# old_motor_line.net
KiCad netlist of a schematic drawn in EAGLE
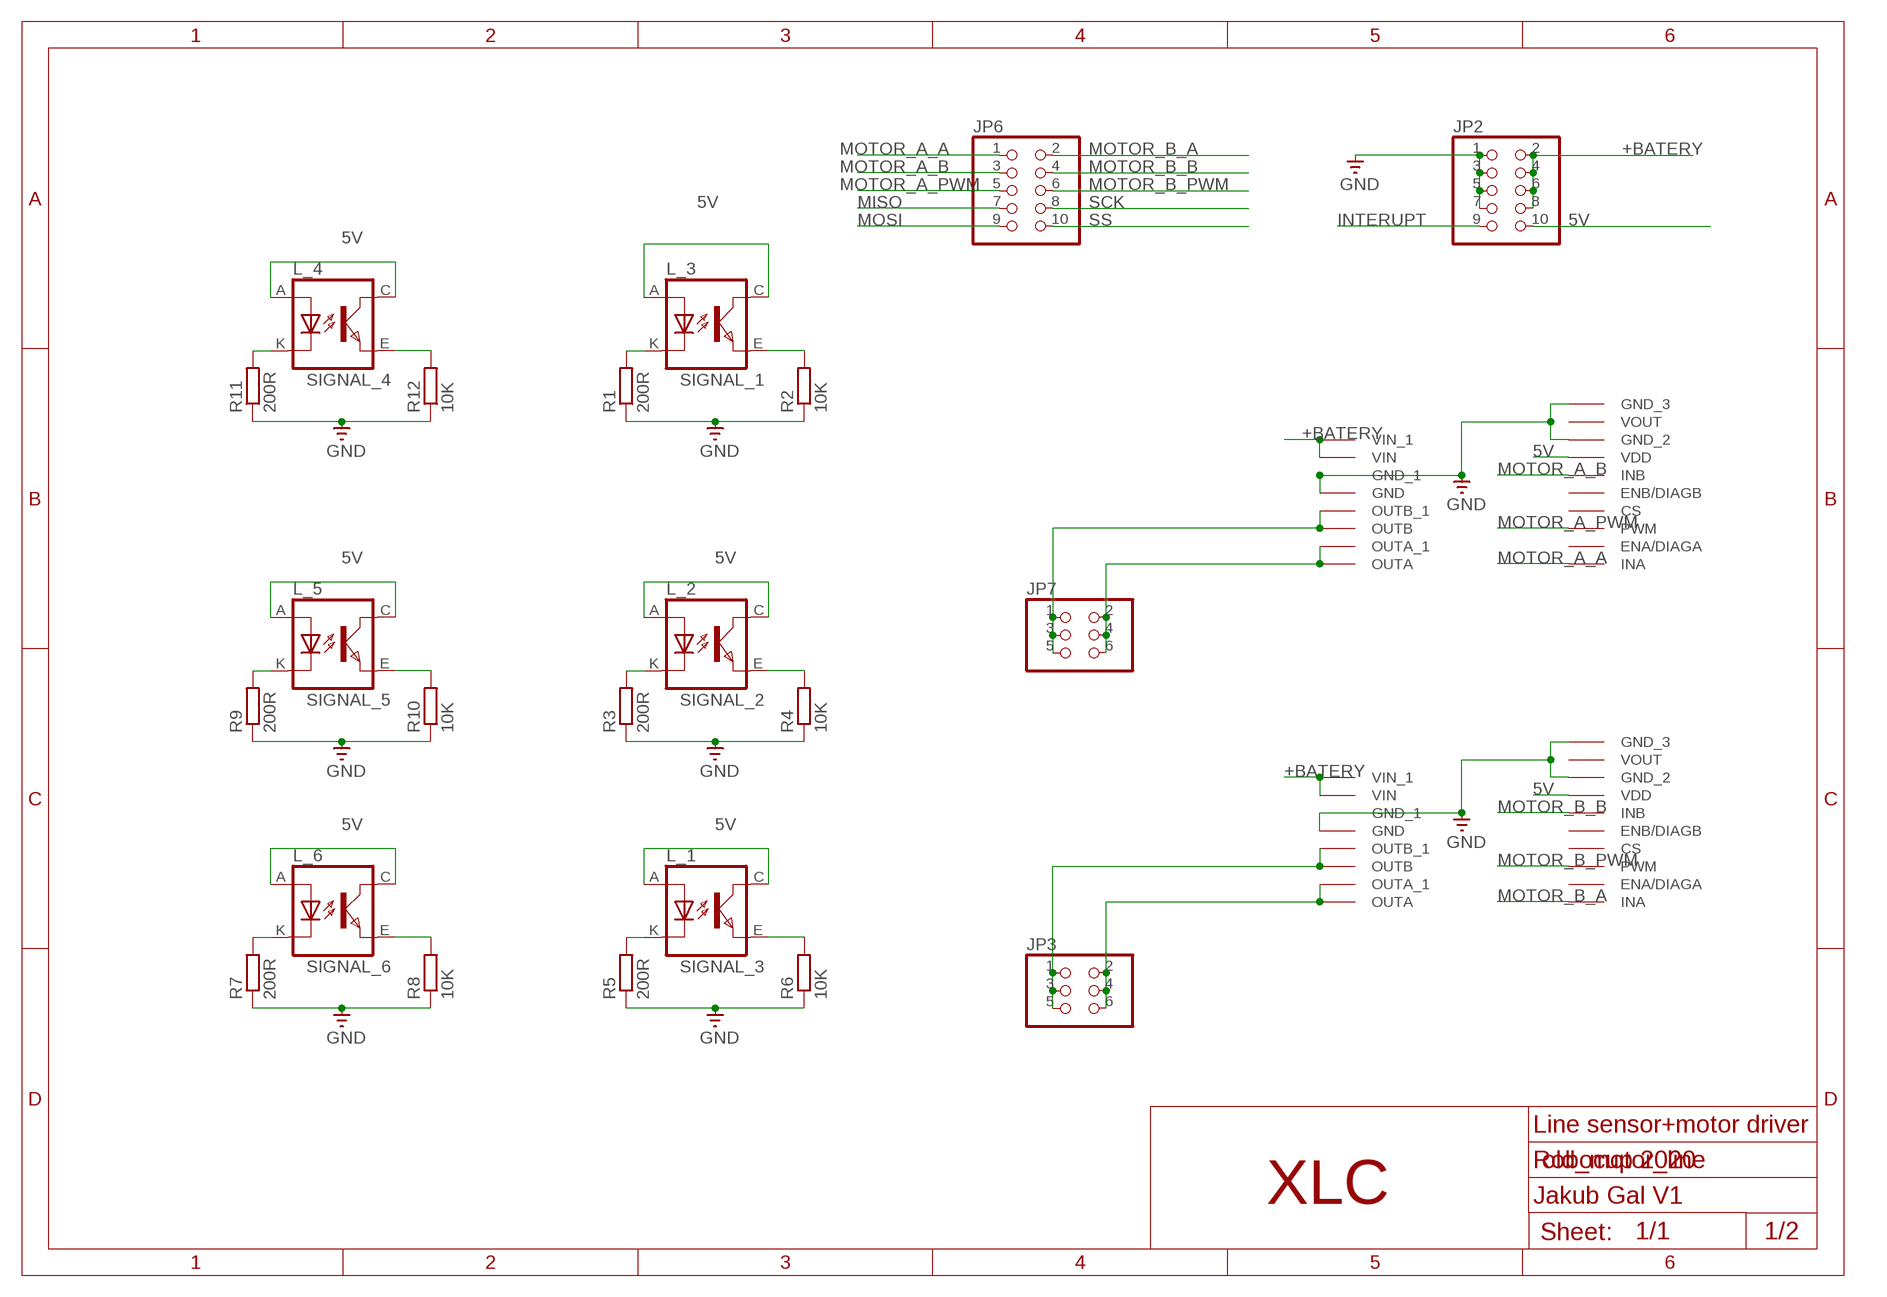
[diagram p0: schematic, sheet 1, part 1 of 2]
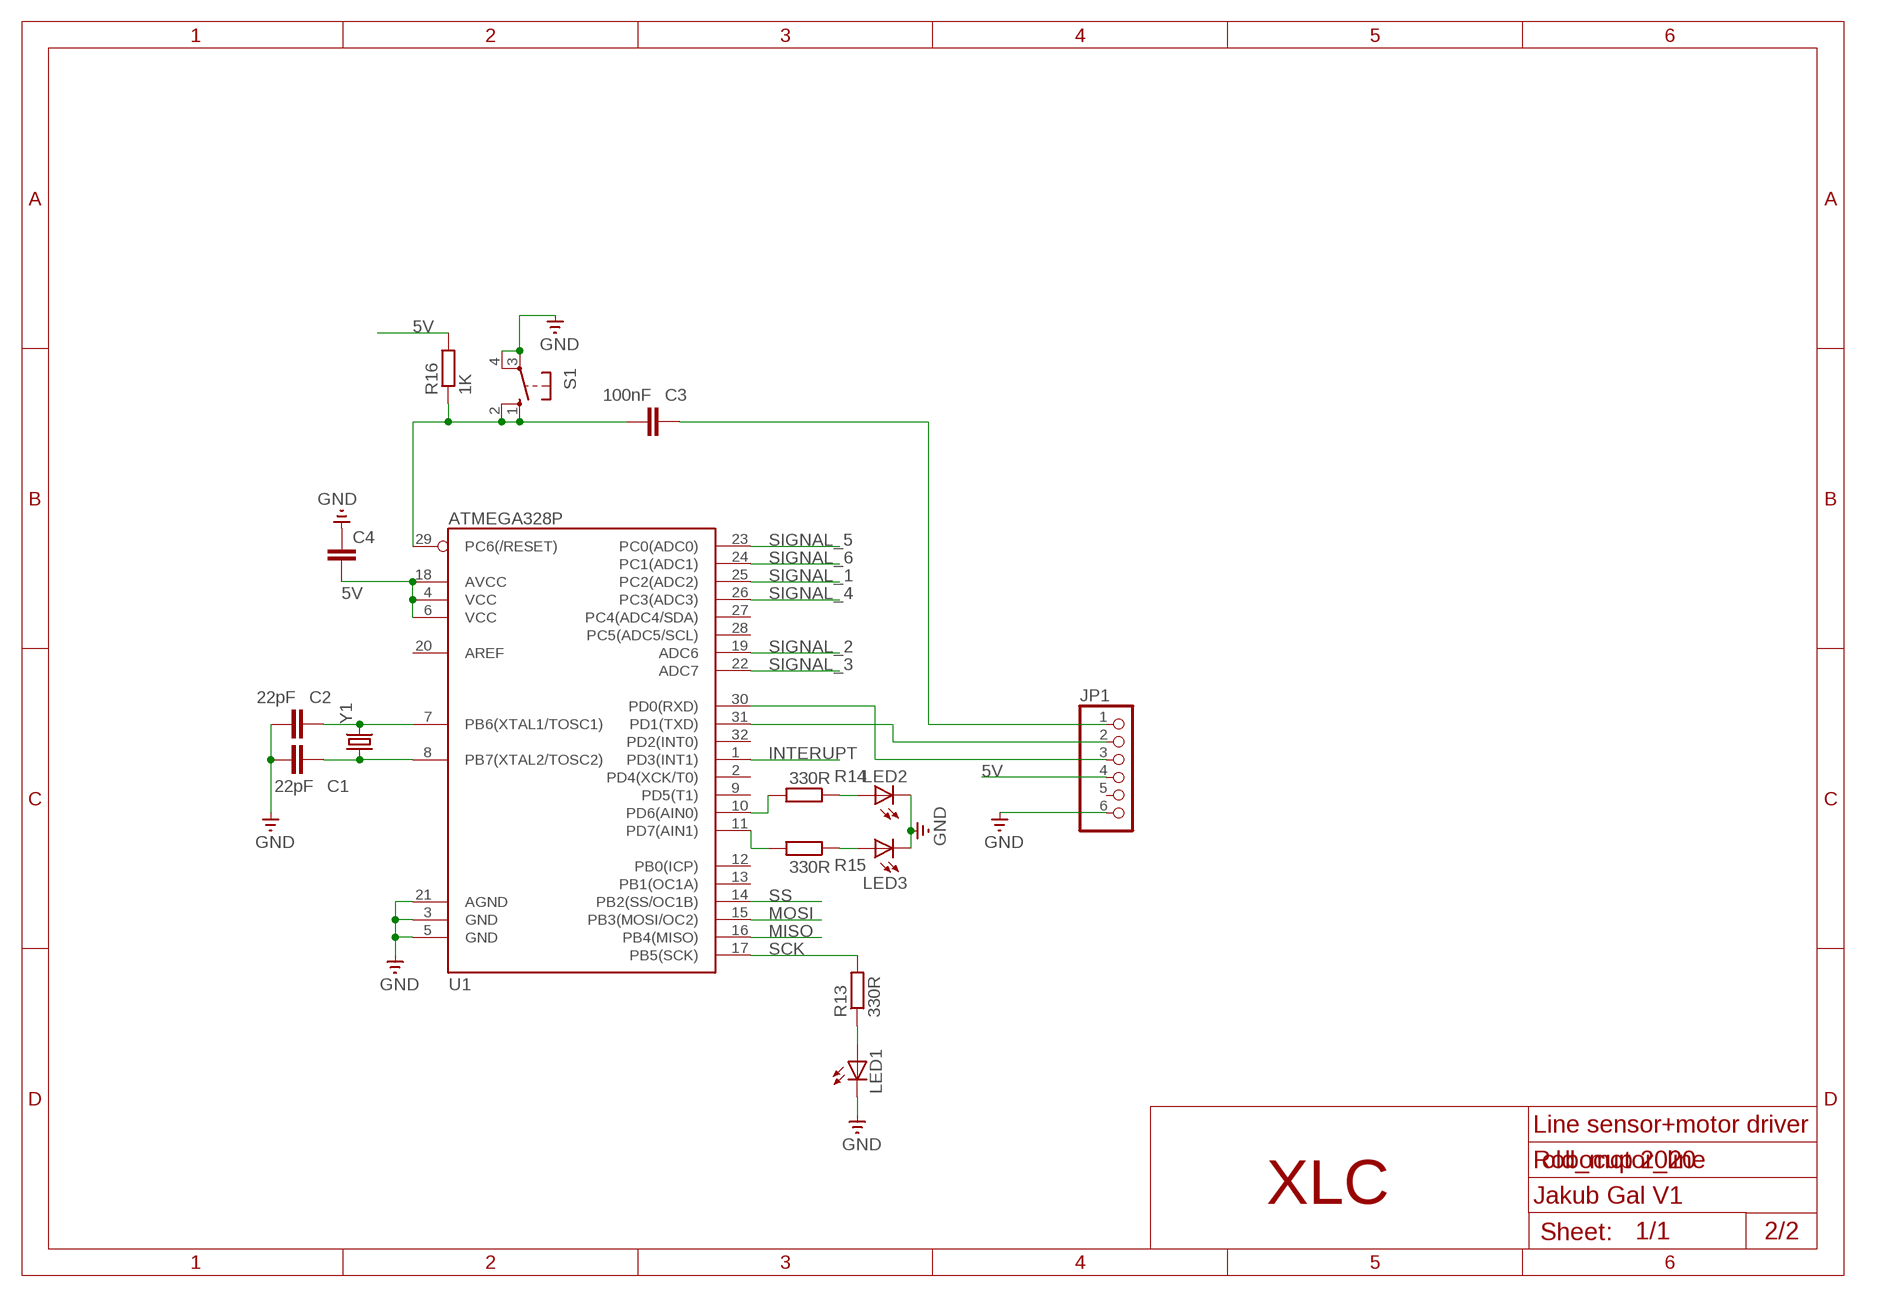
[diagram p1: schematic, sheet 1, part 2 of 2]

(export (version "E")
  (design (tool "Eeschema 10.0.6"))
  (components
    (comp (ref "C1")
      (value "22pF")
      (footprint "eagle-import:C0603")
      (libsource (lib "eagle-import") (part "rcl@1_C-EUC0603"))
    )
    (comp (ref "C2")
      (value "22pF")
      (footprint "eagle-import:C0603")
      (libsource (lib "eagle-import") (part "rcl@1_C-EUC0603"))
    )
    (comp (ref "C3")
      (value "100nF")
      (footprint "eagle-import:C0603")
      (libsource (lib "eagle-import") (part "rcl@1_C-EUC0603"))
    )
    (comp (ref "C4")
      (value "C-EUC0603")
      (footprint "eagle-import:C0603")
      (libsource (lib "eagle-import") (part "C-EUC0603"))
    )
    (comp (ref "JP1")
      (value "PINHD-1X6/90")
      (footprint "eagle-import:1X06_90")
      (libsource (lib "eagle-import") (part "PINHD-1X6/90"))
    )
    (comp (ref "JP2")
      (value "PINHD-2X5IDC")
      (footprint "eagle-import:2X05_IDC")
      (libsource (lib "eagle-import") (part "PINHD-2X5IDC"))
    )
    (comp (ref "JP3")
      (value "PINHD-2X3IDC")
      (footprint "eagle-import:2X03_IDC")
      (libsource (lib "eagle-import") (part "PINHD-2X3IDC"))
    )
    (comp (ref "JP6")
      (value "PINHD-2X5IDC")
      (footprint "eagle-import:2X05_IDC")
      (libsource (lib "eagle-import") (part "PINHD-2X5IDC"))
    )
    (comp (ref "JP7")
      (value "PINHD-2X3IDC")
      (footprint "eagle-import:2X03_IDC")
      (libsource (lib "eagle-import") (part "PINHD-2X3IDC"))
    )
    (comp (ref "LED1")
      (value "LEDCHIPLED_0603")
      (footprint "eagle-import:CHIPLED_0603")
      (libsource (lib "eagle-import") (part "LEDCHIPLED_0603"))
    )
    (comp (ref "LED2")
      (value "LEDCHIPLED_0603")
      (footprint "eagle-import:CHIPLED_0603")
      (libsource (lib "eagle-import") (part "LEDCHIPLED_0603"))
    )
    (comp (ref "LED3")
      (value "LEDCHIPLED_0603")
      (footprint "eagle-import:CHIPLED_0603")
      (libsource (lib "eagle-import") (part "LEDCHIPLED_0603"))
    )
    (comp (ref "L_1")
      (value "TCRT5000")
      (footprint "eagle-import:TCRT5000")
      (libsource (lib "eagle-import") (part "TCRT5000"))
    )
    (comp (ref "L_2")
      (value "TCRT5000")
      (footprint "eagle-import:TCRT5000")
      (libsource (lib "eagle-import") (part "TCRT5000"))
    )
    (comp (ref "L_3")
      (value "TCRT5000")
      (footprint "eagle-import:TCRT5000")
      (libsource (lib "eagle-import") (part "TCRT5000"))
    )
    (comp (ref "L_4")
      (value "TCRT5000")
      (footprint "eagle-import:TCRT5000")
      (fields (field (name "SPICEPREFIX") "O"))
      (libsource (lib "eagle-import") (part "TCRT5000"))
    )
    (comp (ref "L_5")
      (value "TCRT5000")
      (footprint "eagle-import:TCRT5000")
      (libsource (lib "eagle-import") (part "TCRT5000"))
    )
    (comp (ref "L_6")
      (value "TCRT5000")
      (footprint "eagle-import:TCRT5000")
      (fields (field (name "SPICEPREFIX") "O"))
      (libsource (lib "eagle-import") (part "TCRT5000"))
    )
    (comp (ref "R1")
      (value "200R")
      (footprint "eagle-import:R0603")
      (libsource (lib "eagle-import") (part "R-EU_R0603"))
    )
    (comp (ref "R2")
      (value "10K")
      (footprint "eagle-import:R0603")
      (libsource (lib "eagle-import") (part "R-EU_R0603"))
    )
    (comp (ref "R3")
      (value "200R")
      (footprint "eagle-import:R0603")
      (libsource (lib "eagle-import") (part "R-EU_R0603"))
    )
    (comp (ref "R4")
      (value "10K")
      (footprint "eagle-import:R0603")
      (libsource (lib "eagle-import") (part "R-EU_R0603"))
    )
    (comp (ref "R5")
      (value "200R")
      (footprint "eagle-import:R0603")
      (libsource (lib "eagle-import") (part "R-EU_R0603"))
    )
    (comp (ref "R6")
      (value "10K")
      (footprint "eagle-import:R0603")
      (libsource (lib "eagle-import") (part "R-EU_R0603"))
    )
    (comp (ref "R7")
      (value "200R")
      (footprint "eagle-import:R0603")
      (libsource (lib "eagle-import") (part "R-EU_R0603"))
    )
    (comp (ref "R8")
      (value "10K")
      (footprint "eagle-import:R0603")
      (libsource (lib "eagle-import") (part "R-EU_R0603"))
    )
    (comp (ref "R9")
      (value "200R")
      (footprint "eagle-import:R0603")
      (libsource (lib "eagle-import") (part "R-EU_R0603"))
    )
    (comp (ref "R10")
      (value "10K")
      (footprint "eagle-import:R0603")
      (libsource (lib "eagle-import") (part "R-EU_R0603"))
    )
    (comp (ref "R11")
      (value "200R")
      (footprint "eagle-import:R0603")
      (libsource (lib "eagle-import") (part "R-EU_R0603"))
    )
    (comp (ref "R12")
      (value "10K")
      (footprint "eagle-import:R0603")
      (libsource (lib "eagle-import") (part "R-EU_R0603"))
    )
    (comp (ref "R13")
      (value "330R")
      (footprint "eagle-import:R0603")
      (libsource (lib "eagle-import") (part "R-EU_R0603"))
    )
    (comp (ref "R14")
      (value "330R")
      (footprint "eagle-import:R0603")
      (libsource (lib "eagle-import") (part "R-EU_R0603"))
    )
    (comp (ref "R15")
      (value "330R")
      (footprint "eagle-import:R0603")
      (libsource (lib "eagle-import") (part "R-EU_R0603"))
    )
    (comp (ref "R16")
      (value "1K")
      (footprint "eagle-import:R0603")
      (libsource (lib "eagle-import") (part "R-EU_R0603"))
    )
    (comp (ref "S1")
      (value "10-XX")
      (footprint "eagle-import:B3F-10XX")
      (fields (field (name "MPN") "B3F-1000"))
      (libsource (lib "eagle-import") (part "10-XX"))
    )
    (comp (ref "U$1")
      (value "MOTOR_DRIVER")
      (footprint "eagle-import:MOTOR_DRIVER")
      (libsource (lib "eagle-import") (part "MOTOR_DRIVER"))
    )
    (comp (ref "U$2")
      (value "MOTOR_DRIVER")
      (footprint "eagle-import:MOTOR_DRIVER")
      (libsource (lib "eagle-import") (part "MOTOR_DRIVER"))
    )
    (comp (ref "U1")
      (value "ATMEGA328P")
      (footprint "eagle-import:TQFP32-08")
      (libsource (lib "eagle-import") (part "ATMEGA328_SMT"))
    )
    (comp (ref "Y1")
      (value "CRYSTALHC49US")
      (footprint "eagle-import:HC49US")
      (libsource (lib "eagle-import") (part "CRYSTALHC49US"))
    )
  )
  (nets
    (net (code "1") (name "/+BATERY") (class "Default")
      (node (ref "JP2") (pin "2") (pinfunction "2_2") (pintype "passive"))
      (node (ref "JP2") (pin "4") (pinfunction "4_4") (pintype "passive"))
      (node (ref "JP2") (pin "6") (pinfunction "6_6") (pintype "passive"))
      (node (ref "JP2") (pin "8") (pinfunction "8_8") (pintype "passive"))
      (node (ref "U$1") (pin "VIN") (pinfunction "VIN_VIN") (pintype "bidirectional"))
      (node (ref "U$1") (pin "VIN_1") (pinfunction "VIN_1_VIN_1") (pintype "bidirectional"))
      (node (ref "U$2") (pin "VIN") (pinfunction "VIN_VIN") (pintype "bidirectional"))
      (node (ref "U$2") (pin "VIN_1") (pinfunction "VIN_1_VIN_1") (pintype "bidirectional"))
    )
    (net (code "2") (name "/5V") (class "Default")
      (node (ref "C4") (pin "2") (pinfunction "2_2") (pintype "passive"))
      (node (ref "JP1") (pin "4") (pinfunction "4_4") (pintype "passive"))
      (node (ref "JP2") (pin "10") (pinfunction "10_10") (pintype "passive"))
      (node (ref "L_1") (pin "A") (pinfunction "ANODE_A") (pintype "passive"))
      (node (ref "L_1") (pin "C") (pinfunction "COLLECTOR_C") (pintype "passive"))
      (node (ref "L_2") (pin "A") (pinfunction "ANODE_A") (pintype "passive"))
      (node (ref "L_2") (pin "C") (pinfunction "COLLECTOR_C") (pintype "passive"))
      (node (ref "L_3") (pin "A") (pinfunction "ANODE_A") (pintype "passive"))
      (node (ref "L_3") (pin "C") (pinfunction "COLLECTOR_C") (pintype "passive"))
      (node (ref "L_4") (pin "A") (pinfunction "ANODE_A") (pintype "passive"))
      (node (ref "L_4") (pin "C") (pinfunction "COLLECTOR_C") (pintype "passive"))
      (node (ref "L_5") (pin "A") (pinfunction "ANODE_A") (pintype "passive"))
      (node (ref "L_5") (pin "C") (pinfunction "COLLECTOR_C") (pintype "passive"))
      (node (ref "L_6") (pin "A") (pinfunction "ANODE_A") (pintype "passive"))
      (node (ref "L_6") (pin "C") (pinfunction "COLLECTOR_C") (pintype "passive"))
      (node (ref "R16") (pin "2") (pinfunction "2_2") (pintype "passive"))
      (node (ref "U$1") (pin "VDD") (pinfunction "VDD_VDD") (pintype "bidirectional"))
      (node (ref "U$2") (pin "VDD") (pinfunction "VDD_VDD") (pintype "bidirectional"))
      (node (ref "U1") (pin "18") (pinfunction "AVCC_18") (pintype "bidirectional"))
      (node (ref "U1") (pin "4") (pinfunction "VCC_4") (pintype "bidirectional"))
      (node (ref "U1") (pin "6") (pinfunction "VCC_6") (pintype "bidirectional"))
    )
    (net (code "3") (name "/INTERUPT") (class "Default")
      (node (ref "JP2") (pin "9") (pinfunction "9_9") (pintype "passive"))
      (node (ref "U1") (pin "1") (pinfunction "PD3(INT1)_1") (pintype "bidirectional"))
    )
    (net (code "4") (name "/MISO") (class "Default")
      (node (ref "JP6") (pin "7") (pinfunction "7_7") (pintype "passive"))
      (node (ref "U1") (pin "16") (pinfunction "PB4(MISO)_16") (pintype "bidirectional"))
    )
    (net (code "5") (name "/MOSI") (class "Default")
      (node (ref "JP6") (pin "9") (pinfunction "9_9") (pintype "passive"))
      (node (ref "U1") (pin "15") (pinfunction "PB3(MOSI/OC2)_15") (pintype "bidirectional"))
    )
    (net (code "6") (name "/MOTOR_A_A") (class "Default")
      (node (ref "JP6") (pin "1") (pinfunction "1_1") (pintype "passive"))
      (node (ref "U$1") (pin "INA") (pinfunction "INA_INA") (pintype "bidirectional"))
    )
    (net (code "7") (name "/MOTOR_A_B") (class "Default")
      (node (ref "JP6") (pin "3") (pinfunction "3_3") (pintype "passive"))
      (node (ref "U$1") (pin "INB") (pinfunction "INB_INB") (pintype "bidirectional"))
    )
    (net (code "8") (name "/MOTOR_A_PWM") (class "Default")
      (node (ref "JP6") (pin "5") (pinfunction "5_5") (pintype "passive"))
      (node (ref "U$1") (pin "PWM") (pinfunction "PWM_PWM") (pintype "bidirectional"))
    )
    (net (code "9") (name "/MOTOR_B_A") (class "Default")
      (node (ref "JP6") (pin "2") (pinfunction "2_2") (pintype "passive"))
      (node (ref "U$2") (pin "INA") (pinfunction "INA_INA") (pintype "bidirectional"))
    )
    (net (code "10") (name "/MOTOR_B_B") (class "Default")
      (node (ref "JP6") (pin "4") (pinfunction "4_4") (pintype "passive"))
      (node (ref "U$2") (pin "INB") (pinfunction "INB_INB") (pintype "bidirectional"))
    )
    (net (code "11") (name "/MOTOR_B_PWM") (class "Default")
      (node (ref "JP6") (pin "6") (pinfunction "6_6") (pintype "passive"))
      (node (ref "U$2") (pin "PWM") (pinfunction "PWM_PWM") (pintype "bidirectional"))
    )
    (net (code "12") (name "/SCK") (class "Default")
      (node (ref "JP6") (pin "8") (pinfunction "8_8") (pintype "passive"))
      (node (ref "R13") (pin "2") (pinfunction "2_2") (pintype "passive"))
      (node (ref "U1") (pin "17") (pinfunction "PB5(SCK)_17") (pintype "bidirectional"))
    )
    (net (code "13") (name "/SIGNAL_1") (class "Default")
      (node (ref "L_3") (pin "E") (pinfunction "EMITTER_E") (pintype "passive"))
      (node (ref "R2") (pin "2") (pinfunction "2_2") (pintype "passive"))
      (node (ref "U1") (pin "25") (pinfunction "PC2(ADC2)_25") (pintype "bidirectional"))
    )
    (net (code "14") (name "/SIGNAL_2") (class "Default")
      (node (ref "L_2") (pin "E") (pinfunction "EMITTER_E") (pintype "passive"))
      (node (ref "R4") (pin "2") (pinfunction "2_2") (pintype "passive"))
      (node (ref "U1") (pin "19") (pinfunction "ADC6_19") (pintype "bidirectional"))
    )
    (net (code "15") (name "/SIGNAL_3") (class "Default")
      (node (ref "L_1") (pin "E") (pinfunction "EMITTER_E") (pintype "passive"))
      (node (ref "R6") (pin "2") (pinfunction "2_2") (pintype "passive"))
      (node (ref "U1") (pin "22") (pinfunction "ADC7_22") (pintype "bidirectional"))
    )
    (net (code "16") (name "/SIGNAL_4") (class "Default")
      (node (ref "L_4") (pin "E") (pinfunction "EMITTER_E") (pintype "passive"))
      (node (ref "R12") (pin "2") (pinfunction "2_2") (pintype "passive"))
      (node (ref "U1") (pin "26") (pinfunction "PC3(ADC3)_26") (pintype "bidirectional"))
    )
    (net (code "17") (name "/SIGNAL_5") (class "Default")
      (node (ref "L_5") (pin "E") (pinfunction "EMITTER_E") (pintype "passive"))
      (node (ref "R10") (pin "2") (pinfunction "2_2") (pintype "passive"))
      (node (ref "U1") (pin "23") (pinfunction "PC0(ADC0)_23") (pintype "bidirectional"))
    )
    (net (code "18") (name "/SIGNAL_6") (class "Default")
      (node (ref "L_6") (pin "E") (pinfunction "EMITTER_E") (pintype "passive"))
      (node (ref "R8") (pin "2") (pinfunction "2_2") (pintype "passive"))
      (node (ref "U1") (pin "24") (pinfunction "PC1(ADC1)_24") (pintype "bidirectional"))
    )
    (net (code "19") (name "/SS") (class "Default")
      (node (ref "JP6") (pin "10") (pinfunction "10_10") (pintype "passive"))
      (node (ref "U1") (pin "14") (pinfunction "PB2(SS/OC1B)_14") (pintype "bidirectional"))
    )
    (net (code "20") (name "GND") (class "Default")
      (node (ref "C1") (pin "1") (pinfunction "1_1") (pintype "passive"))
      (node (ref "C2") (pin "1") (pinfunction "1_1") (pintype "passive"))
      (node (ref "C4") (pin "1") (pinfunction "1_1") (pintype "passive"))
      (node (ref "JP1") (pin "6") (pinfunction "6_6") (pintype "passive"))
      (node (ref "JP2") (pin "1") (pinfunction "1_1") (pintype "passive"))
      (node (ref "JP2") (pin "3") (pinfunction "3_3") (pintype "passive"))
      (node (ref "JP2") (pin "5") (pinfunction "5_5") (pintype "passive"))
      (node (ref "JP2") (pin "7") (pinfunction "7_7") (pintype "passive"))
      (node (ref "LED1") (pin "C") (pinfunction "C_C") (pintype "passive"))
      (node (ref "LED2") (pin "C") (pinfunction "C_C") (pintype "passive"))
      (node (ref "LED3") (pin "C") (pinfunction "C_C") (pintype "passive"))
      (node (ref "R1") (pin "1") (pinfunction "1_1") (pintype "passive"))
      (node (ref "R10") (pin "1") (pinfunction "1_1") (pintype "passive"))
      (node (ref "R11") (pin "1") (pinfunction "1_1") (pintype "passive"))
      (node (ref "R12") (pin "1") (pinfunction "1_1") (pintype "passive"))
      (node (ref "R2") (pin "1") (pinfunction "1_1") (pintype "passive"))
      (node (ref "R3") (pin "1") (pinfunction "1_1") (pintype "passive"))
      (node (ref "R4") (pin "1") (pinfunction "1_1") (pintype "passive"))
      (node (ref "R5") (pin "1") (pinfunction "1_1") (pintype "passive"))
      (node (ref "R6") (pin "1") (pinfunction "1_1") (pintype "passive"))
      (node (ref "R7") (pin "1") (pinfunction "1_1") (pintype "passive"))
      (node (ref "R8") (pin "1") (pinfunction "1_1") (pintype "passive"))
      (node (ref "R9") (pin "1") (pinfunction "1_1") (pintype "passive"))
      (node (ref "S1") (pin "3") (pinfunction "P_3") (pintype "passive"))
      (node (ref "S1") (pin "4") (pinfunction "P1_4") (pintype "passive"))
      (node (ref "U$1") (pin "GND") (pinfunction "GND_GND") (pintype "bidirectional"))
      (node (ref "U$1") (pin "GND_1") (pinfunction "GND_1_GND_1") (pintype "bidirectional"))
      (node (ref "U$1") (pin "GND_2") (pinfunction "GND_2_GND_2") (pintype "bidirectional"))
      (node (ref "U$1") (pin "GND_3") (pinfunction "GND_3_GND_3") (pintype "bidirectional"))
      (node (ref "U$2") (pin "GND") (pinfunction "GND_GND") (pintype "bidirectional"))
      (node (ref "U$2") (pin "GND_1") (pinfunction "GND_1_GND_1") (pintype "bidirectional"))
      (node (ref "U$2") (pin "GND_2") (pinfunction "GND_2_GND_2") (pintype "bidirectional"))
      (node (ref "U$2") (pin "GND_3") (pinfunction "GND_3_GND_3") (pintype "bidirectional"))
      (node (ref "U1") (pin "21") (pinfunction "AGND_21") (pintype "bidirectional"))
      (node (ref "U1") (pin "3") (pinfunction "GND_3") (pintype "bidirectional"))
      (node (ref "U1") (pin "5") (pinfunction "GND_5") (pintype "bidirectional"))
    )
    (net (code "21") (name "Net-(C3-Pad2)") (class "Default")
      (node (ref "C3") (pin "2") (pinfunction "2_2") (pintype "passive"))
      (node (ref "JP1") (pin "1") (pinfunction "1_1") (pintype "passive"))
    )
    (net (code "22") (name "Net-(JP3-Pad1)") (class "Default")
      (node (ref "JP3") (pin "1") (pinfunction "1_1") (pintype "passive"))
      (node (ref "JP3") (pin "3") (pinfunction "3_3") (pintype "passive"))
      (node (ref "JP3") (pin "5") (pinfunction "5_5") (pintype "passive"))
      (node (ref "U$2") (pin "OUTB") (pinfunction "OUTB_OUTB") (pintype "bidirectional"))
      (node (ref "U$2") (pin "OUTB_1") (pinfunction "OUTB_1_OUTB_1") (pintype "bidirectional"))
    )
    (net (code "23") (name "Net-(JP3-Pad2)") (class "Default")
      (node (ref "JP3") (pin "2") (pinfunction "2_2") (pintype "passive"))
      (node (ref "JP3") (pin "4") (pinfunction "4_4") (pintype "passive"))
      (node (ref "JP3") (pin "6") (pinfunction "6_6") (pintype "passive"))
      (node (ref "U$2") (pin "OUTA") (pinfunction "OUTA_OUTA") (pintype "bidirectional"))
      (node (ref "U$2") (pin "OUTA_1") (pinfunction "OUTA_1_OUTA_1") (pintype "bidirectional"))
    )
    (net (code "24") (name "Net-(JP7-Pad1)") (class "Default")
      (node (ref "JP7") (pin "1") (pinfunction "1_1") (pintype "passive"))
      (node (ref "JP7") (pin "3") (pinfunction "3_3") (pintype "passive"))
      (node (ref "JP7") (pin "5") (pinfunction "5_5") (pintype "passive"))
      (node (ref "U$1") (pin "OUTB") (pinfunction "OUTB_OUTB") (pintype "bidirectional"))
      (node (ref "U$1") (pin "OUTB_1") (pinfunction "OUTB_1_OUTB_1") (pintype "bidirectional"))
    )
    (net (code "25") (name "Net-(JP7-Pad2)") (class "Default")
      (node (ref "JP7") (pin "2") (pinfunction "2_2") (pintype "passive"))
      (node (ref "JP7") (pin "4") (pinfunction "4_4") (pintype "passive"))
      (node (ref "JP7") (pin "6") (pinfunction "6_6") (pintype "passive"))
      (node (ref "U$1") (pin "OUTA") (pinfunction "OUTA_OUTA") (pintype "bidirectional"))
      (node (ref "U$1") (pin "OUTA_1") (pinfunction "OUTA_1_OUTA_1") (pintype "bidirectional"))
    )
    (net (code "26") (name "Net-(LED1-PadA)") (class "Default")
      (node (ref "LED1") (pin "A") (pinfunction "A_A") (pintype "passive"))
      (node (ref "R13") (pin "1") (pinfunction "1_1") (pintype "passive"))
    )
    (net (code "27") (name "Net-(LED2-PadA)") (class "Default")
      (node (ref "LED2") (pin "A") (pinfunction "A_A") (pintype "passive"))
      (node (ref "R14") (pin "1") (pinfunction "1_1") (pintype "passive"))
    )
    (net (code "28") (name "Net-(LED3-PadA)") (class "Default")
      (node (ref "LED3") (pin "A") (pinfunction "A_A") (pintype "passive"))
      (node (ref "R15") (pin "1") (pinfunction "1_1") (pintype "passive"))
    )
    (net (code "29") (name "Net-(L_1-CATHODE)") (class "Default")
      (node (ref "L_1") (pin "K") (pinfunction "CATHODE_K") (pintype "passive"))
      (node (ref "R5") (pin "2") (pinfunction "2_2") (pintype "passive"))
    )
    (net (code "30") (name "Net-(L_2-CATHODE)") (class "Default")
      (node (ref "L_2") (pin "K") (pinfunction "CATHODE_K") (pintype "passive"))
      (node (ref "R3") (pin "2") (pinfunction "2_2") (pintype "passive"))
    )
    (net (code "31") (name "Net-(L_3-CATHODE)") (class "Default")
      (node (ref "L_3") (pin "K") (pinfunction "CATHODE_K") (pintype "passive"))
      (node (ref "R1") (pin "2") (pinfunction "2_2") (pintype "passive"))
    )
    (net (code "32") (name "Net-(L_4-CATHODE)") (class "Default")
      (node (ref "L_4") (pin "K") (pinfunction "CATHODE_K") (pintype "passive"))
      (node (ref "R11") (pin "2") (pinfunction "2_2") (pintype "passive"))
    )
    (net (code "33") (name "Net-(L_5-CATHODE)") (class "Default")
      (node (ref "L_5") (pin "K") (pinfunction "CATHODE_K") (pintype "passive"))
      (node (ref "R9") (pin "2") (pinfunction "2_2") (pintype "passive"))
    )
    (net (code "34") (name "Net-(L_6-CATHODE)") (class "Default")
      (node (ref "L_6") (pin "K") (pinfunction "CATHODE_K") (pintype "passive"))
      (node (ref "R7") (pin "2") (pinfunction "2_2") (pintype "passive"))
    )
    (net (code "35") (name "Net-(S1-S)") (class "Default")
      (node (ref "C3") (pin "1") (pinfunction "1_1") (pintype "passive"))
      (node (ref "R16") (pin "1") (pinfunction "1_1") (pintype "passive"))
      (node (ref "S1") (pin "1") (pinfunction "S_1") (pintype "passive"))
      (node (ref "S1") (pin "2") (pinfunction "S1_2") (pintype "passive"))
      (node (ref "U1") (pin "29") (pinfunction "PC6(/RESET)_29") (pintype "bidirectional"))
    )
    (net (code "36") (name "Net-(U1-PB6(XTAL1{slash}TOSC1))") (class "Default")
      (node (ref "C2") (pin "2") (pinfunction "2_2") (pintype "passive"))
      (node (ref "U1") (pin "7") (pinfunction "PB6(XTAL1/TOSC1)_7") (pintype "bidirectional"))
      (node (ref "Y1") (pin "2") (pinfunction "2_2") (pintype "passive"))
    )
    (net (code "37") (name "Net-(U1-PB7(XTAL2{slash}TOSC2))") (class "Default")
      (node (ref "C1") (pin "2") (pinfunction "2_2") (pintype "passive"))
      (node (ref "U1") (pin "8") (pinfunction "PB7(XTAL2/TOSC2)_8") (pintype "bidirectional"))
      (node (ref "Y1") (pin "1") (pinfunction "1_1") (pintype "passive"))
    )
    (net (code "38") (name "Net-(U1-PD0(RXD))") (class "Default")
      (node (ref "JP1") (pin "3") (pinfunction "3_3") (pintype "passive"))
      (node (ref "U1") (pin "30") (pinfunction "PD0(RXD)_30") (pintype "bidirectional"))
    )
    (net (code "39") (name "Net-(U1-PD1(TXD))") (class "Default")
      (node (ref "JP1") (pin "2") (pinfunction "2_2") (pintype "passive"))
      (node (ref "U1") (pin "31") (pinfunction "PD1(TXD)_31") (pintype "bidirectional"))
    )
    (net (code "40") (name "Net-(U1-PD6(AIN0))") (class "Default")
      (node (ref "R14") (pin "2") (pinfunction "2_2") (pintype "passive"))
      (node (ref "U1") (pin "10") (pinfunction "PD6(AIN0)_10") (pintype "bidirectional"))
    )
    (net (code "41") (name "Net-(U1-PD7(AIN1))") (class "Default")
      (node (ref "R15") (pin "2") (pinfunction "2_2") (pintype "passive"))
      (node (ref "U1") (pin "11") (pinfunction "PD7(AIN1)_11") (pintype "bidirectional"))
    )
    (net (code "42") (name "unconnected-(JP1-Pad5)") (class "Default")
      (node (ref "JP1") (pin "5") (pinfunction "5_5") (pintype "passive"))
    )
    (net (code "43") (name "unconnected-(U$1-PadCS)") (class "Default")
      (node (ref "U$1") (pin "CS") (pinfunction "CS_CS") (pintype "bidirectional"))
    )
    (net (code "44") (name "unconnected-(U$1-PadENA{slash}DIAGA)") (class "Default")
      (node (ref "U$1") (pin "ENA/DIAGA") (pinfunction "ENA/DIAGA_ENA/DIAGA") (pintype "bidirectional"))
    )
    (net (code "45") (name "unconnected-(U$1-PadENB{slash}DIAGB)") (class "Default")
      (node (ref "U$1") (pin "ENB/DIAGB") (pinfunction "ENB/DIAGB_ENB/DIAGB") (pintype "bidirectional"))
    )
    (net (code "46") (name "unconnected-(U$1-PadVOUT)") (class "Default")
      (node (ref "U$1") (pin "VOUT") (pinfunction "VOUT_VOUT") (pintype "bidirectional"))
    )
    (net (code "47") (name "unconnected-(U$2-PadCS)") (class "Default")
      (node (ref "U$2") (pin "CS") (pinfunction "CS_CS") (pintype "bidirectional"))
    )
    (net (code "48") (name "unconnected-(U$2-PadENA{slash}DIAGA)") (class "Default")
      (node (ref "U$2") (pin "ENA/DIAGA") (pinfunction "ENA/DIAGA_ENA/DIAGA") (pintype "bidirectional"))
    )
    (net (code "49") (name "unconnected-(U$2-PadENB{slash}DIAGB)") (class "Default")
      (node (ref "U$2") (pin "ENB/DIAGB") (pinfunction "ENB/DIAGB_ENB/DIAGB") (pintype "bidirectional"))
    )
    (net (code "50") (name "unconnected-(U$2-PadVOUT)") (class "Default")
      (node (ref "U$2") (pin "VOUT") (pinfunction "VOUT_VOUT") (pintype "bidirectional"))
    )
    (net (code "51") (name "unconnected-(U1-AREF-Pad20)") (class "Default")
      (node (ref "U1") (pin "20") (pinfunction "AREF_20") (pintype "bidirectional"))
    )
    (net (code "52") (name "unconnected-(U1-PB0(ICP)-Pad12)") (class "Default")
      (node (ref "U1") (pin "12") (pinfunction "PB0(ICP)_12") (pintype "bidirectional"))
    )
    (net (code "53") (name "unconnected-(U1-PB1(OC1A)-Pad13)") (class "Default")
      (node (ref "U1") (pin "13") (pinfunction "PB1(OC1A)_13") (pintype "bidirectional"))
    )
    (net (code "54") (name "unconnected-(U1-PC4(ADC4{slash}SDA)-Pad27)") (class "Default")
      (node (ref "U1") (pin "27") (pinfunction "PC4(ADC4/SDA)_27") (pintype "bidirectional"))
    )
    (net (code "55") (name "unconnected-(U1-PC5(ADC5{slash}SCL)-Pad28)") (class "Default")
      (node (ref "U1") (pin "28") (pinfunction "PC5(ADC5/SCL)_28") (pintype "bidirectional"))
    )
    (net (code "56") (name "unconnected-(U1-PD2(INT0)-Pad32)") (class "Default")
      (node (ref "U1") (pin "32") (pinfunction "PD2(INT0)_32") (pintype "bidirectional"))
    )
    (net (code "57") (name "unconnected-(U1-PD4(XCK{slash}T0)-Pad2)") (class "Default")
      (node (ref "U1") (pin "2") (pinfunction "PD4(XCK/T0)_2") (pintype "bidirectional"))
    )
    (net (code "58") (name "unconnected-(U1-PD5(T1)-Pad9)") (class "Default")
      (node (ref "U1") (pin "9") (pinfunction "PD5(T1)_9") (pintype "bidirectional"))
    )
  )
)
